# power.net
KiCad netlist of a schematic drawn in Altium Designer
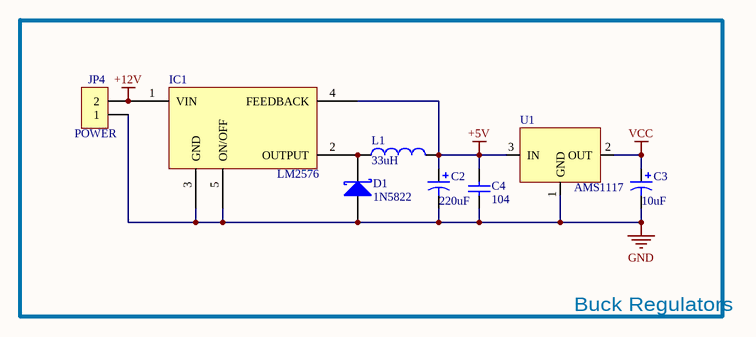
[diagram p0: power.SchDoc]

(export (version "E")
  (design (tool "Eeschema 10.0.6"))
  (components
    (comp (ref "C2")
      (value "220uF")
      (footprint "CM E(8*10.2)")
      (description "Polarized Capacitor (Radial)")
      (fields (field (name "PUBLISHER") "Altium Limited"))
      (libsource (lib "Miscellaneous Devices") (part "Cap Pol1"))
    )
    (comp (ref "C3")
      (value "10uF")
      (footprint "CD A(3216)")
      (description "Polarized Capacitor (Radial)")
      (fields (field (name "PUBLISHER") "Altium Limited"))
      (libsource (lib "Miscellaneous Devices") (part "Cap Pol1"))
    )
    (comp (ref "C4")
      (value "104")
      (footprint "C 0603_L")
      (description "Capacitor")
      (fields (field (name "PUBLISHER") "Altium Limited"))
      (libsource (lib "Miscellaneous Devices") (part "Cap"))
    )
    (comp (ref "D1")
      (value "1N5822")
      (footprint "DO_201_AD")
      (description "Schottky Rectifier")
      (fields (field (name "PUBLISHER") "Altium Limited"))
      (libsource (lib "Miscellaneous Devices") (part "Diode 11DQ03"))
    )
    (comp (ref "IC1")
      (value "LM2576")
      (footprint "TO263-5A")
      (description "稳压")
      (libsource (lib "Chip") (part "LM2576"))
    )
    (comp (ref "JP4")
      (value "POWER")
      (footprint "KF128-5.08-2P")
      (description "2P接插件")
      (fields (field (name "版权归属") "源创客"))
      (libsource (lib "4.10 - 接插件-脚距5.08") (part "Header 2"))
    )
    (comp (ref "L1")
      (value "33uH")
      (footprint "CDRH127")
      (description "Inductor")
      (fields (field (name "PUBLISHER") "Altium Limited"))
      (libsource (lib "Miscellaneous Devices") (part "Inductor"))
    )
    (comp (ref "U1") (value "AMS1117") (footprint "SOT_223") (libsource (lib "主控板载芯片") (part "AMS1117")))
  )
  (nets
    (net (code "1") (name "+5V") (class "Default")
      (node (ref "C2") (pin "1") (pinfunction "1_1") (pintype "passive"))
      (node (ref "C4") (pin "2") (pinfunction "2_2") (pintype "passive"))
      (node (ref "IC1") (pin "4") (pinfunction "FEEDBACK_4") (pintype "passive"))
      (node (ref "L1") (pin "2") (pinfunction "2_2") (pintype "passive"))
      (node (ref "U1") (pin "3") (pinfunction "IN_3") (pintype "passive"))
    )
    (net (code "2") (name "+12V") (class "Default")
      (node (ref "IC1") (pin "1") (pinfunction "VIN_1") (pintype "passive"))
      (node (ref "JP4") (pin "2") (pinfunction "2_2") (pintype "passive"))
    )
    (net (code "3") (name "GND") (class "Default")
      (node (ref "C2") (pin "2") (pinfunction "2_2") (pintype "passive"))
      (node (ref "C3") (pin "2") (pinfunction "2_2") (pintype "passive"))
      (node (ref "C4") (pin "1") (pinfunction "1_1") (pintype "passive"))
      (node (ref "D1") (pin "1") (pinfunction "A_1") (pintype "passive"))
      (node (ref "IC1") (pin "3") (pinfunction "GND_3") (pintype "passive"))
      (node (ref "IC1") (pin "5") (pinfunction "ON/OFF_5") (pintype "passive"))
      (node (ref "JP4") (pin "1") (pinfunction "1_1") (pintype "passive"))
      (node (ref "U1") (pin "1") (pinfunction "GND_1") (pintype "passive"))
    )
    (net (code "4") (name "Net-(D1-K)") (class "Default")
      (node (ref "D1") (pin "2") (pinfunction "K_2") (pintype "passive"))
      (node (ref "IC1") (pin "2") (pinfunction "OUTPUT_2") (pintype "passive"))
      (node (ref "L1") (pin "1") (pinfunction "1_1") (pintype "passive"))
    )
    (net (code "5") (name "VCC") (class "Default")
      (node (ref "C3") (pin "1") (pinfunction "1_1") (pintype "passive"))
      (node (ref "U1") (pin "2") (pinfunction "OUT_2") (pintype "passive"))
    )
  )
)
